# Schematic_Small_Unit_Altium.net
KiCad netlist of a schematic drawn in Altium Designer
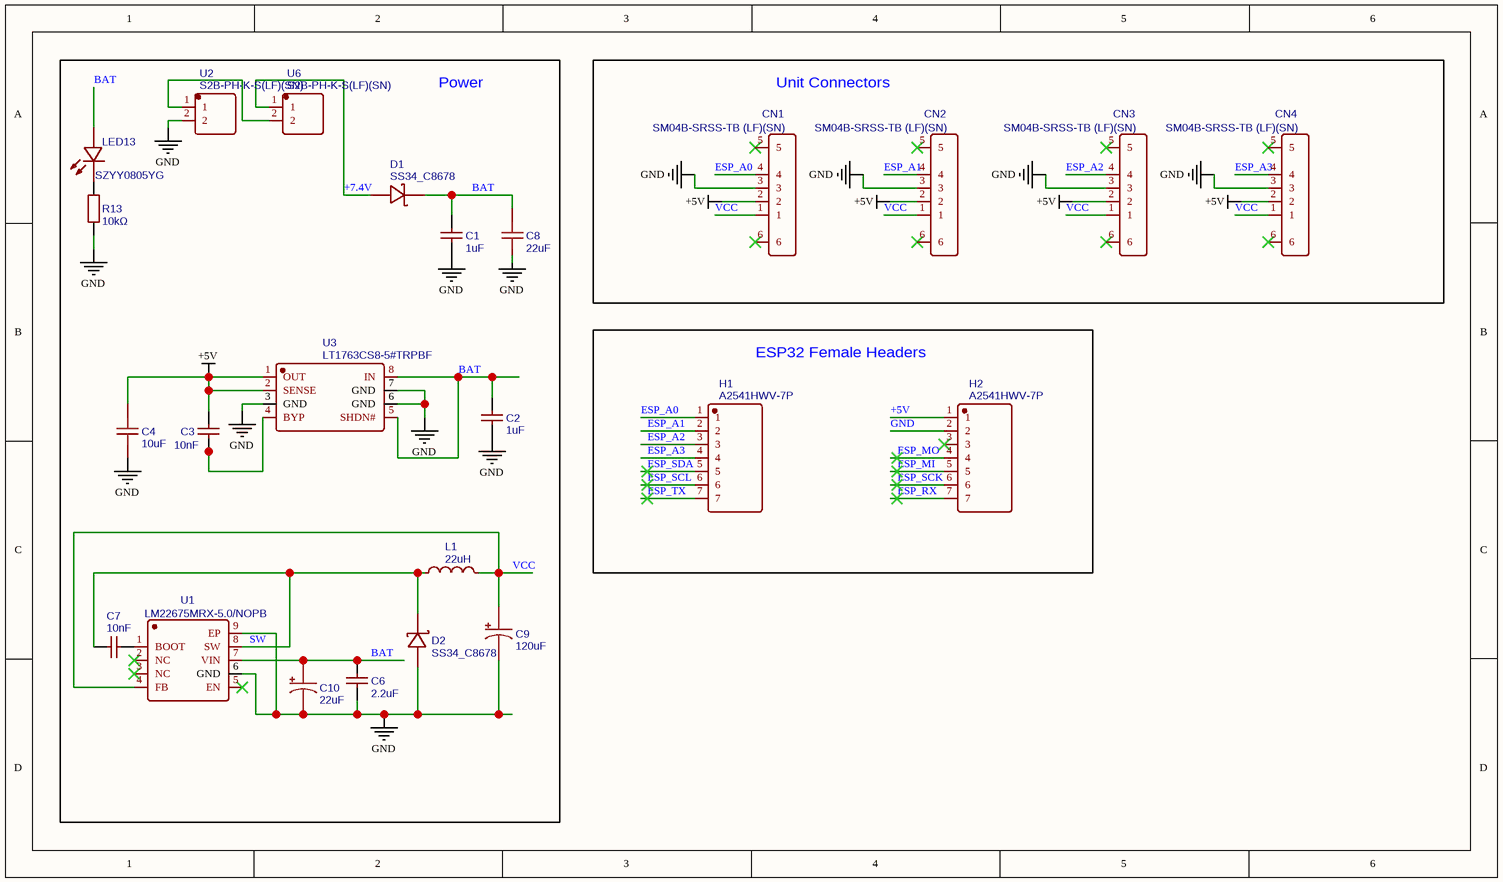
[diagram p0: Schematic_Small_Unit_Altium.schdoc]

(export (version "E")
  (design (tool "Eeschema 10.0.6"))
  (components
    (comp (ref "C1")
      (value "1uF")
      (fields
        (field (name "MANUFACTURER PART") "CL21B105KBFNNNE")
        (field (name "MANUFACTURER") "SAMSUNG(三星)")
      )
      (libsource (lib "altium-import") (part "root_1_1uF_"))
    )
    (comp (ref "C2")
      (value "1uF")
      (fields
        (field (name "MANUFACTURER PART") "CL21B105KBFNNNE")
        (field (name "MANUFACTURER") "SAMSUNG(三星)")
      )
      (libsource (lib "altium-import") (part "root_1_1uF_"))
    )
    (comp (ref "C3")
      (value "10nF")
      (fields
        (field (name "MANUFACTURER PART") "CL05B103KB5NNNC")
        (field (name "MANUFACTURER") "SAMSUNG(三星)")
      )
      (libsource (lib "altium-import") (part "root_1_10nF_"))
    )
    (comp (ref "C4")
      (value "10uF")
      (fields
        (field (name "MANUFACTURER") "SAMSUNG(三星)")
        (field (name "MANUFACTURER PART") "CL10A106KP8NNNC")
      )
      (libsource (lib "altium-import") (part "root_1_10uF_"))
    )
    (comp (ref "C6")
      (value "2.2uF")
      (fields
        (field (name "MANUFACTURER PART") "CL10A225KO8NNNC")
        (field (name "MANUFACTURER") "SAMSUNG(三星)")
      )
      (libsource (lib "altium-import") (part "root_3_2.2uF_"))
    )
    (comp (ref "C7")
      (value "10nF")
      (fields
        (field (name "MANUFACTURER PART") "CL05B103KB5NNNC")
        (field (name "MANUFACTURER") "SAMSUNG(三星)")
      )
      (libsource (lib "altium-import") (part "root_0_10nF_"))
    )
    (comp (ref "C8")
      (value "22uF")
      (fields
        (field (name "MANUFACTURER") "SAMSUNG(三星)")
        (field (name "MANUFACTURER PART") "CL21A226MAYNNNE")
        (field (name "CONTRIBUTOR") "LCSC")
      )
      (libsource (lib "altium-import") (part "root_1_22uF_"))
    )
    (comp (ref "C9")
      (value "120uF")
      (fields
        (field (name "MANUFACTURER") "PANASONIC(松下)")
        (field (name "MANUFACTURER PART") "10SVPC120MV")
        (field (name "CONTRIBUTOR") "LCSC")
      )
      (libsource (lib "altium-import") (part "root_0_120uF_"))
    )
    (comp (ref "C10")
      (value "22uF")
      (fields
        (field (name "MANUFACTURER") "ROQANG(容强)")
        (field (name "MANUFACTURER PART") "VT1V220M0505")
        (field (name "CONTRIBUTOR") "LCSC")
      )
      (libsource (lib "altium-import") (part "root_0_22uF_"))
    )
    (comp (ref "CN1")
      (value "SM04B-SRSS-TB (LF)(SN)")
      (fields
        (field (name "MANUFACTURER") "JST")
        (field (name "MANUFACTURER PART") "SM04B-SRSS-TB(LF)(SN)")
        (field (name "CONTRIBUTOR") "LCSC")
      )
      (libsource (lib "altium-import") (part "root_1_SM04B-SRSS-TB (LF)(SN)_"))
    )
    (comp (ref "CN2")
      (value "SM04B-SRSS-TB (LF)(SN)")
      (fields
        (field (name "MANUFACTURER") "JST")
        (field (name "MANUFACTURER PART") "SM04B-SRSS-TB(LF)(SN)")
        (field (name "CONTRIBUTOR") "LCSC")
      )
      (libsource (lib "altium-import") (part "root_1_SM04B-SRSS-TB (LF)(SN)_"))
    )
    (comp (ref "CN3")
      (value "SM04B-SRSS-TB (LF)(SN)")
      (fields
        (field (name "MANUFACTURER") "JST")
        (field (name "MANUFACTURER PART") "SM04B-SRSS-TB(LF)(SN)")
        (field (name "CONTRIBUTOR") "LCSC")
      )
      (libsource (lib "altium-import") (part "root_1_SM04B-SRSS-TB (LF)(SN)_"))
    )
    (comp (ref "CN4")
      (value "SM04B-SRSS-TB (LF)(SN)")
      (fields
        (field (name "MANUFACTURER") "JST")
        (field (name "MANUFACTURER PART") "SM04B-SRSS-TB(LF)(SN)")
        (field (name "CONTRIBUTOR") "LCSC")
      )
      (libsource (lib "altium-import") (part "root_1_SM04B-SRSS-TB (LF)(SN)_"))
    )
    (comp (ref "D1")
      (value "SS34_C8678")
      (fields (field (name "MANUFACTURER PART") "SS34") (field (name "MANUFACTURER") "MDD(辰达半导体)"))
      (libsource (lib "altium-import") (part "root_2_SS34_C8678_"))
    )
    (comp (ref "D2")
      (value "SS34_C8678")
      (fields (field (name "MANUFACTURER PART") "SS34") (field (name "MANUFACTURER") "MDD(辰达半导体)"))
      (libsource (lib "altium-import") (part "root_3_SS34_C8678_"))
    )
    (comp (ref "H1")
      (value "A2541HWV-7P")
      (fields (field (name "MANUFACTURER") "CJT(长江连接器)") (field (name "CONTRIBUTOR") "LCSC"))
      (libsource (lib "altium-import") (part "root_0_A2541HWV-7P_"))
    )
    (comp (ref "H2")
      (value "A2541HWV-7P")
      (fields (field (name "MANUFACTURER") "CJT(长江连接器)") (field (name "CONTRIBUTOR") "LCSC"))
      (libsource (lib "altium-import") (part "root_0_A2541HWV-7P_"))
    )
    (comp (ref "L1")
      (value "22uH")
      (fields (field (name "MANUFACTURER") "FH(风华)") (field (name "MANUFACTURER PART") "PRS6020-220MT"))
      (libsource (lib "altium-import") (part "root_0_22uH_"))
    )
    (comp (ref "LED13")
      (value "SZYY0805YG")
      (fields (field (name "MANUFACTURER") "yongyu(永裕光电)") (field (name "CONTRIBUTOR") "LCSC"))
      (libsource (lib "altium-import") (part "root_1_SZYY0805YG_"))
    )
    (comp (ref "R13")
      (value "10kΩ")
      (fields
        (field (name "MANUFACTURER") "UNI-ROYAL(厚声)")
        (field (name "MANUFACTURER PART") "0805W8F1002T5E")
      )
      (libsource (lib "altium-import") (part "root_1_10kΩ_"))
    )
    (comp (ref "U1")
      (value "LM22675MRX-5.0/NOPB")
      (fields (field (name "MANUFACTURER") "TI(德州仪器)") (field (name "CONTRIBUTOR") "LCSC"))
      (libsource (lib "altium-import") (part "root_0_LM22675MRX-5.0/NOPB_"))
    )
    (comp (ref "U2")
      (value "S2B-PH-K-S(LF)(SN)")
      (fields (field (name "MANUFACTURER") "JST") (field (name "CONTRIBUTOR") "LCSC"))
      (libsource (lib "altium-import") (part "root_0_S2B-PH-K-S(LF)(SN)_"))
    )
    (comp (ref "U3")
      (value "LT1763CS8-5#TRPBF")
      (fields (field (name "MANUFACTURER") "ADI(亚德诺)") (field (name "CONTRIBUTOR") "LCSC"))
      (libsource (lib "altium-import") (part "root_0_LT1763CS8-5#TRPBF_"))
    )
    (comp (ref "U6")
      (value "S2B-PH-K-S(LF)(SN)")
      (fields (field (name "MANUFACTURER") "JST") (field (name "CONTRIBUTOR") "LCSC"))
      (libsource (lib "altium-import") (part "root_0_S2B-PH-K-S(LF)(SN)_"))
    )
  )
  (nets
    (net (code "1") (name "+5V") (class "Default")
      (node (ref "C3") (pin "2") (pinfunction "2_2") (pintype "passive"))
      (node (ref "C4") (pin "2") (pinfunction "2_2") (pintype "passive"))
      (node (ref "CN1") (pin "2") (pinfunction "2_2") (pintype "passive"))
      (node (ref "CN2") (pin "2") (pinfunction "2_2") (pintype "passive"))
      (node (ref "CN3") (pin "2") (pinfunction "2_2") (pintype "passive"))
      (node (ref "CN4") (pin "2") (pinfunction "2_2") (pintype "passive"))
      (node (ref "H2") (pin "1") (pinfunction "1_1") (pintype "passive"))
      (node (ref "U3") (pin "1") (pinfunction "OUT_1") (pintype "passive"))
      (node (ref "U3") (pin "2") (pinfunction "SENSE_2") (pintype "passive"))
    )
    (net (code "2") (name "/+7.4V") (class "Default")
      (node (ref "D1") (pin "2") (pinfunction "A_2") (pintype "passive"))
      (node (ref "U6") (pin "1") (pinfunction "1_1") (pintype "passive"))
    )
    (net (code "3") (name "/BAT") (class "Default")
      (node (ref "C1") (pin "2") (pinfunction "2_2") (pintype "passive"))
      (node (ref "C10") (pin "1") (pinfunction "1_1") (pintype "passive"))
      (node (ref "C2") (pin "2") (pinfunction "2_2") (pintype "passive"))
      (node (ref "C6") (pin "1") (pinfunction "1_1") (pintype "passive"))
      (node (ref "C8") (pin "2") (pinfunction "2_2") (pintype "passive"))
      (node (ref "D1") (pin "1") (pinfunction "K_1") (pintype "passive"))
      (node (ref "LED13") (pin "1") (pinfunction "+_1") (pintype "passive"))
      (node (ref "U1") (pin "7") (pinfunction "VIN_7") (pintype "passive"))
      (node (ref "U3") (pin "5") (pinfunction "SHDN#_5") (pintype "passive"))
      (node (ref "U3") (pin "8") (pinfunction "IN_8") (pintype "passive"))
    )
    (net (code "4") (name "/ESP_A0") (class "Default")
      (node (ref "CN1") (pin "4") (pinfunction "4_4") (pintype "passive"))
      (node (ref "H1") (pin "1") (pinfunction "1_1") (pintype "passive"))
    )
    (net (code "5") (name "/ESP_A1") (class "Default")
      (node (ref "CN2") (pin "4") (pinfunction "4_4") (pintype "passive"))
      (node (ref "H1") (pin "2") (pinfunction "2_2") (pintype "passive"))
    )
    (net (code "6") (name "/ESP_A2") (class "Default")
      (node (ref "CN3") (pin "4") (pinfunction "4_4") (pintype "passive"))
      (node (ref "H1") (pin "3") (pinfunction "3_3") (pintype "passive"))
    )
    (net (code "7") (name "/ESP_A3") (class "Default")
      (node (ref "CN4") (pin "4") (pinfunction "4_4") (pintype "passive"))
      (node (ref "H1") (pin "4") (pinfunction "4_4") (pintype "passive"))
    )
    (net (code "8") (name "/ESP_MI") (class "Default")
      (node (ref "H2") (pin "5") (pinfunction "5_5") (pintype "passive"))
    )
    (net (code "9") (name "/ESP_MO") (class "Default")
      (node (ref "H2") (pin "4") (pinfunction "4_4") (pintype "passive"))
    )
    (net (code "10") (name "/ESP_RX") (class "Default")
      (node (ref "H2") (pin "7") (pinfunction "7_7") (pintype "passive"))
    )
    (net (code "11") (name "/ESP_SCK") (class "Default")
      (node (ref "H2") (pin "6") (pinfunction "6_6") (pintype "passive"))
    )
    (net (code "12") (name "/ESP_SCL") (class "Default")
      (node (ref "H1") (pin "6") (pinfunction "6_6") (pintype "passive"))
    )
    (net (code "13") (name "/ESP_SDA") (class "Default")
      (node (ref "H1") (pin "5") (pinfunction "5_5") (pintype "passive"))
    )
    (net (code "14") (name "/ESP_TX") (class "Default")
      (node (ref "H1") (pin "7") (pinfunction "7_7") (pintype "passive"))
    )
    (net (code "15") (name "/SW") (class "Default")
      (node (ref "C7") (pin "1") (pinfunction "1_1") (pintype "passive"))
      (node (ref "D2") (pin "1") (pinfunction "K_1") (pintype "passive"))
      (node (ref "L1") (pin "1") (pinfunction "1_1") (pintype "passive"))
      (node (ref "U1") (pin "8") (pinfunction "SW_8") (pintype "passive"))
    )
    (net (code "16") (name "/VCC") (class "Default")
      (node (ref "C9") (pin "1") (pinfunction "1_1") (pintype "passive"))
      (node (ref "CN1") (pin "1") (pinfunction "1_1") (pintype "passive"))
      (node (ref "CN2") (pin "1") (pinfunction "1_1") (pintype "passive"))
      (node (ref "CN3") (pin "1") (pinfunction "1_1") (pintype "passive"))
      (node (ref "CN4") (pin "1") (pinfunction "1_1") (pintype "passive"))
      (node (ref "L1") (pin "2") (pinfunction "2_2") (pintype "passive"))
      (node (ref "U1") (pin "4") (pinfunction "FB_4") (pintype "passive"))
    )
    (net (code "17") (name "GND") (class "Default")
      (node (ref "C1") (pin "1") (pinfunction "1_1") (pintype "passive"))
      (node (ref "C10") (pin "2") (pinfunction "2_2") (pintype "passive"))
      (node (ref "C2") (pin "1") (pinfunction "1_1") (pintype "passive"))
      (node (ref "C4") (pin "1") (pinfunction "1_1") (pintype "passive"))
      (node (ref "C6") (pin "2") (pinfunction "2_2") (pintype "passive"))
      (node (ref "C8") (pin "1") (pinfunction "1_1") (pintype "passive"))
      (node (ref "C9") (pin "2") (pinfunction "2_2") (pintype "passive"))
      (node (ref "CN1") (pin "3") (pinfunction "3_3") (pintype "passive"))
      (node (ref "CN2") (pin "3") (pinfunction "3_3") (pintype "passive"))
      (node (ref "CN3") (pin "3") (pinfunction "3_3") (pintype "passive"))
      (node (ref "CN4") (pin "3") (pinfunction "3_3") (pintype "passive"))
      (node (ref "D2") (pin "2") (pinfunction "A_2") (pintype "passive"))
      (node (ref "H2") (pin "2") (pinfunction "2_2") (pintype "passive"))
      (node (ref "R13") (pin "1") (pinfunction "1_1") (pintype "passive"))
      (node (ref "U1") (pin "6") (pinfunction "GND_6") (pintype "passive"))
      (node (ref "U1") (pin "9") (pinfunction "EP_9") (pintype "passive"))
      (node (ref "U2") (pin "2") (pinfunction "2_2") (pintype "passive"))
      (node (ref "U3") (pin "3") (pinfunction "GND_3") (pintype "passive"))
      (node (ref "U3") (pin "6") (pinfunction "GND_6") (pintype "passive"))
      (node (ref "U3") (pin "7") (pinfunction "GND_7") (pintype "passive"))
    )
    (net (code "18") (name "Net-(LED13--)") (class "Default")
      (node (ref "LED13") (pin "2") (pinfunction "-_2") (pintype "passive"))
      (node (ref "R13") (pin "2") (pinfunction "2_2") (pintype "passive"))
    )
    (net (code "19") (name "Net-(U1-BOOT)") (class "Default")
      (node (ref "C7") (pin "2") (pinfunction "2_2") (pintype "passive"))
      (node (ref "U1") (pin "1") (pinfunction "BOOT_1") (pintype "passive"))
    )
    (net (code "20") (name "Net-(U2-Pad1)") (class "Default")
      (node (ref "U2") (pin "1") (pinfunction "1_1") (pintype "passive"))
      (node (ref "U6") (pin "2") (pinfunction "2_2") (pintype "passive"))
    )
    (net (code "21") (name "Net-(U3-BYP)") (class "Default")
      (node (ref "C3") (pin "1") (pinfunction "1_1") (pintype "passive"))
      (node (ref "U3") (pin "4") (pinfunction "BYP_4") (pintype "passive"))
    )
    (net (code "22") (name "unconnected-(CN1-Pad5)") (class "Default")
      (node (ref "CN1") (pin "5") (pinfunction "5_5") (pintype "passive+no_connect"))
    )
    (net (code "23") (name "unconnected-(CN1-Pad6)") (class "Default")
      (node (ref "CN1") (pin "6") (pinfunction "6_6") (pintype "passive+no_connect"))
    )
    (net (code "24") (name "unconnected-(CN2-Pad5)") (class "Default")
      (node (ref "CN2") (pin "5") (pinfunction "5_5") (pintype "passive+no_connect"))
    )
    (net (code "25") (name "unconnected-(CN2-Pad6)") (class "Default")
      (node (ref "CN2") (pin "6") (pinfunction "6_6") (pintype "passive+no_connect"))
    )
    (net (code "26") (name "unconnected-(CN3-Pad5)") (class "Default")
      (node (ref "CN3") (pin "5") (pinfunction "5_5") (pintype "passive+no_connect"))
    )
    (net (code "27") (name "unconnected-(CN3-Pad6)") (class "Default")
      (node (ref "CN3") (pin "6") (pinfunction "6_6") (pintype "passive+no_connect"))
    )
    (net (code "28") (name "unconnected-(CN4-Pad5)") (class "Default")
      (node (ref "CN4") (pin "5") (pinfunction "5_5") (pintype "passive+no_connect"))
    )
    (net (code "29") (name "unconnected-(CN4-Pad6)") (class "Default")
      (node (ref "CN4") (pin "6") (pinfunction "6_6") (pintype "passive+no_connect"))
    )
    (net (code "30") (name "unconnected-(H2-Pad3)") (class "Default")
      (node (ref "H2") (pin "3") (pinfunction "3_3") (pintype "passive+no_connect"))
    )
    (net (code "31") (name "unconnected-(U1-EN-Pad5)") (class "Default")
      (node (ref "U1") (pin "5") (pinfunction "EN_5") (pintype "passive+no_connect"))
    )
    (net (code "32") (name "unconnected-(U1-NC-Pad2)") (class "Default")
      (node (ref "U1") (pin "2") (pinfunction "NC_2") (pintype "passive+no_connect"))
    )
    (net (code "33") (name "unconnected-(U1-NC-Pad3)") (class "Default")
      (node (ref "U1") (pin "3") (pinfunction "NC_3") (pintype "passive+no_connect"))
    )
  )
)
